# lab01sol.net
KiCad netlist of a schematic drawn in EAGLE
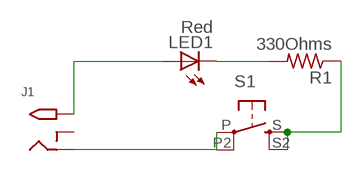
[diagram p0: schematic, sheet 1]

(export (version "E")
  (design (tool "Eeschema 10.0.6"))
  (components
    (comp (ref "J1")
      (value "2.1MMJACKTHM")
      (footprint "eagle-import:PJ-102A")
      (fields (field (name "CREATOR") "Swanson") (field (name "REVIEWER") "Swanson"))
      (libsource (lib "eagle-import") (part "2.1MMJACKTHM"))
    )
    (comp (ref "LED1")
      (value "Red")
      (footprint "eagle-import:LED5MM")
      (fields (field (name "CREATOR") "Swanson") (field (name "REVIEWER") "Swanson"))
      (libsource (lib "eagle-import") (part "LED5MM"))
    )
    (comp (ref "R1")
      (value "330Ohms")
      (footprint "eagle-import:RESAD1160W55L680D260_HS")
      (fields (field (name "CREATOR") "Swanson") (field (name "REVIEWER") "Swanson"))
      (libsource (lib "eagle-import") (part "RESISTORTH-1/4W-CARBON"))
    )
    (comp (ref "S1")
      (value "BUTTON-TACTILE-SQUARE")
      (footprint "eagle-import:BUTTON-TACTILE-SQUARE-ADAFRUIT1010")
      (fields (field (name "CREATOR") "Swanson") (field (name "REVIEWER") "Swanson"))
      (libsource (lib "eagle-import") (part "BUTTON-TACTILE-SQUARE"))
    )
  )
  (nets
    (net (code "1") (name "Net-(J1-PadTIP)") (class "Default")
      (node (ref "J1") (pin "TIP") (pinfunction "TIP_TIP") (pintype "bidirectional"))
      (node (ref "LED1") (pin "A") (pinfunction "A_A") (pintype "passive"))
    )
    (net (code "2") (name "Net-(LED1-C)") (class "Default")
      (node (ref "LED1") (pin "K") (pinfunction "C_K") (pintype "passive"))
      (node (ref "R1") (pin "2") (pinfunction "2_2") (pintype "passive"))
    )
    (net (code "3") (name "Net-(S1-P1)") (class "Default")
      (node (ref "J1") (pin "RING") (pinfunction "RING_RING") (pintype "bidirectional"))
      (node (ref "S1") (pin "P") (pinfunction "P_P") (pintype "passive"))
      (node (ref "S1") (pin "P2") (pinfunction "P1_P2") (pintype "passive"))
    )
    (net (code "4") (name "Net-(S1-S1)") (class "Default")
      (node (ref "R1") (pin "1") (pinfunction "1_1") (pintype "passive"))
      (node (ref "S1") (pin "S") (pinfunction "S_S") (pintype "passive"))
      (node (ref "S1") (pin "S2") (pinfunction "S1_S2") (pintype "passive"))
    )
    (net (code "5") (name "unconnected-(J1-PadRING_SW)") (class "Default")
      (node (ref "J1") (pin "RING_SW") (pinfunction "RING_SW_RING_SW") (pintype "bidirectional"))
    )
  )
)
